# 3_power.net
KiCad netlist of a schematic drawn in Altium Designer
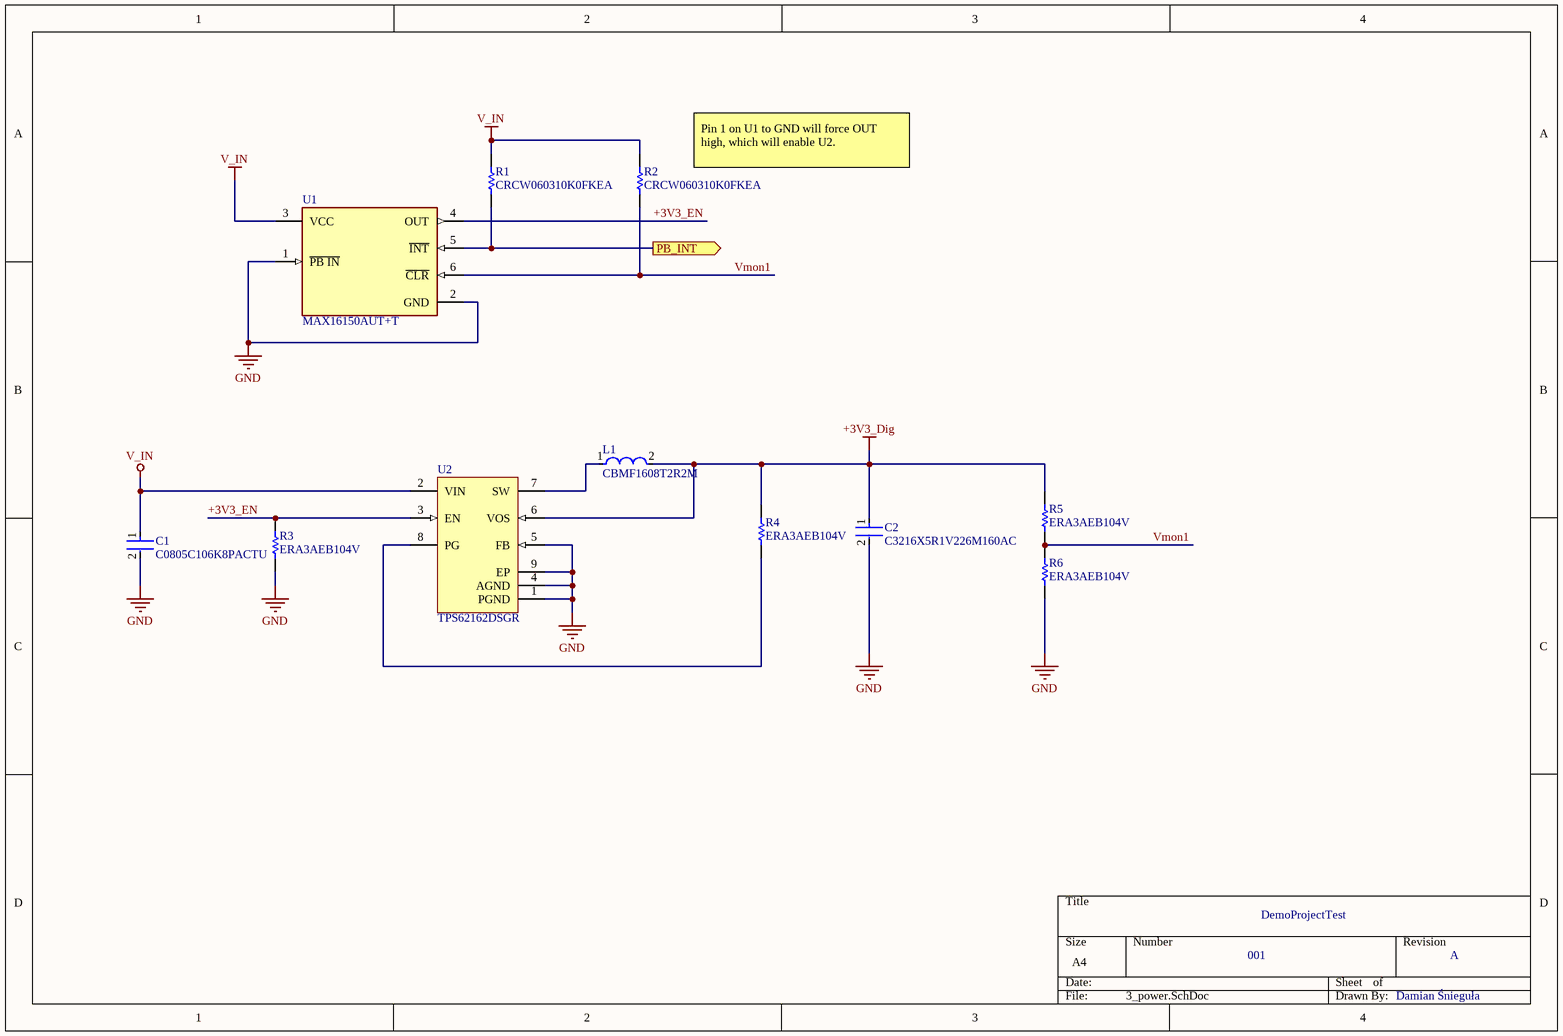
[diagram p0: 3_power.SchDoc]

(export (version "E")
  (design (tool "Eeschema 10.0.6"))
  (components
    (comp (ref "C1")
      (value "C0805C106K8PACTU")
      (footprint "FP-C0805C-DG-MFG")
      (description "SMD Comm X5R, Ceramic, 10 uF, 10%, 10 V, X5R, SMD, MLCC, Temperature Stable, Class II, 0805")
      (fields (field (name "TOLERANCE") "10%"))
      (libsource (lib "Altium Content Vault") (part "11868f565c42a9108669ba33697ecf6"))
    )
    (comp (ref "C2")
      (value "C3216X5R1V226M160AC")
      (footprint "FP-C3216-160-0_2-IPC_B")
      (description "Multilayer Ceramic Capacitors 22uF ±20% 35V X5R SMD 1206")
      (fields (field (name "TOLERANCE") "20%") (field (name "VOLTAGE") "35V"))
      (libsource (lib "Altium Content Vault") (part "11868f565c42a9108669ba33697ecf6"))
    )
    (comp (ref "L1")
      (value "CBMF1608T2R2M")
      (footprint "FP-CBMF1608-MFG")
      (description "SMD Inductors 2.2uH ±20% 0.56A 0.221Ω 0603")
      (fields (field (name "TOLERANCE") "20%"))
      (libsource (lib "Altium Content Vault") (part "725321dda6339637d4d059423bc1c3c"))
    )
    (comp (ref "R1")
      (value "CRCW060310K0FKEA")
      (footprint "RESC1609X50X30NL8T20")
      (description "Chip Resistor, 10 KOhm, +/- 1%, 100 mW, -55 to 155 degC, 0603 (1608 Metric), RoHS, Tape and Reel")
      (fields (field (name "MANUFACTURER") "Vishay Semiconductor"))
      (libsource (lib "Altium Content Vault") (part "RES-2"))
    )
    (comp (ref "R2")
      (value "CRCW060310K0FKEA")
      (footprint "RESC1609X50X30NL8T20")
      (description "Chip Resistor, 10 KOhm, +/- 1%, 100 mW, -55 to 155 degC, 0603 (1608 Metric), RoHS, Tape and Reel")
      (fields (field (name "MANUFACTURER") "Vishay Semiconductor"))
      (libsource (lib "Altium Content Vault") (part "RES-2"))
    )
    (comp (ref "R3")
      (value "ERA3AEB104V")
      (footprint "RESC1608X55X30ML20T20")
      (fields (field (name "MANUFACTURER") "Panasonic"))
      (libsource (lib "Altium Content Vault") (part "RES"))
    )
    (comp (ref "R4")
      (value "ERA3AEB104V")
      (footprint "RESC1608X55X30ML20T20")
      (fields (field (name "MANUFACTURER") "Panasonic"))
      (libsource (lib "Altium Content Vault") (part "RES"))
    )
    (comp (ref "R5")
      (value "ERA3AEB104V")
      (footprint "RESC1608X55X30ML20T20")
      (fields (field (name "MANUFACTURER") "Panasonic"))
      (libsource (lib "Altium Content Vault") (part "RES"))
    )
    (comp (ref "R6")
      (value "ERA3AEB104V")
      (footprint "RESC1608X55X30ML20T20")
      (fields (field (name "MANUFACTURER") "Panasonic"))
      (libsource (lib "Altium Content Vault") (part "RES"))
    )
    (comp (ref "U1")
      (value "MAX16150AUT+T")
      (footprint "FP-U6-1-MFG")
      (description "IC SUPERVISOR 1 CHANNEL SOT23-6")
      (libsource (lib "Altium Content Vault") (part "36a392858d03d148bb8ce7f45f4b5f9"))
    )
    (comp (ref "U2")
      (value "TPS62162DSGR")
      (footprint "DSG0008A_V")
      (fields (field (name "MANUFACTURER") "Texas Instruments"))
      (libsource (lib "Altium Content Vault") (part "TI-TPS62162DSG8-1600X900TP"))
    )
  )
  (nets
    (net (code "1") (name "+3V3_Dig") (class "Default")
      (node (ref "C2") (pin "1") (pinfunction "1_1") (pintype "passive"))
      (node (ref "L1") (pin "2") (pinfunction "2_2") (pintype "passive"))
      (node (ref "R4") (pin "2") (pinfunction "2_2") (pintype "passive"))
      (node (ref "R5") (pin "2") (pinfunction "2_2") (pintype "passive"))
      (node (ref "U2") (pin "6") (pinfunction "VOS_6") (pintype "input"))
    )
    (net (code "2") (name "/+3V3_EN") (class "Default")
      (node (ref "R3") (pin "2") (pinfunction "2_2") (pintype "passive"))
      (node (ref "U1") (pin "4") (pinfunction "OUT_4") (pintype "output"))
      (node (ref "U2") (pin "3") (pinfunction "EN_3") (pintype "input"))
    )
    (net (code "3") (name "/PB_INT") (class "Default")
      (node (ref "R1") (pin "1") (pinfunction "1_1") (pintype "passive"))
      (node (ref "U1") (pin "5") (pinfunction "~{INT}_5") (pintype "input"))
    )
    (net (code "4") (name "/Vmon1") (class "Default")
      (node (ref "R2") (pin "1") (pinfunction "1_1") (pintype "passive"))
      (node (ref "R5") (pin "1") (pinfunction "1_1") (pintype "passive"))
      (node (ref "R6") (pin "2") (pinfunction "2_2") (pintype "passive"))
      (node (ref "U1") (pin "6") (pinfunction "~{CLR}_6") (pintype "input"))
    )
    (net (code "5") (name "GND") (class "Default")
      (node (ref "C1") (pin "2") (pinfunction "2_2") (pintype "passive"))
      (node (ref "C2") (pin "2") (pinfunction "2_2") (pintype "passive"))
      (node (ref "R3") (pin "1") (pinfunction "1_1") (pintype "passive"))
      (node (ref "R6") (pin "1") (pinfunction "1_1") (pintype "passive"))
      (node (ref "U1") (pin "1") (pinfunction "~{PB_IN}_1") (pintype "input"))
      (node (ref "U1") (pin "2") (pinfunction "GND_2") (pintype "power_in"))
      (node (ref "U2") (pin "1") (pinfunction "PGND_1") (pintype "power_in"))
      (node (ref "U2") (pin "4") (pinfunction "AGND_4") (pintype "power_in"))
      (node (ref "U2") (pin "5") (pinfunction "FB_5") (pintype "input"))
      (node (ref "U2") (pin "9") (pinfunction "EP_9") (pintype "power_in"))
    )
    (net (code "6") (name "Net-(U2-PG)") (class "Default")
      (node (ref "R4") (pin "1") (pinfunction "1_1") (pintype "passive"))
      (node (ref "U2") (pin "8") (pinfunction "PG_8") (pintype "tri_state"))
    )
    (net (code "7") (name "Net-(U2-SW)") (class "Default")
      (node (ref "L1") (pin "1") (pinfunction "1_1") (pintype "passive"))
      (node (ref "U2") (pin "7") (pinfunction "SW_7") (pintype "power_in"))
    )
    (net (code "8") (name "V_IN") (class "Default")
      (node (ref "C1") (pin "1") (pinfunction "1_1") (pintype "passive"))
      (node (ref "R1") (pin "2") (pinfunction "2_2") (pintype "passive"))
      (node (ref "R2") (pin "2") (pinfunction "2_2") (pintype "passive"))
      (node (ref "U1") (pin "3") (pinfunction "VCC_3") (pintype "power_in"))
      (node (ref "U2") (pin "2") (pinfunction "VIN_2") (pintype "power_in"))
    )
  )
)
